# simpleCH552_finished.net
KiCad netlist of a schematic drawn in EAGLE
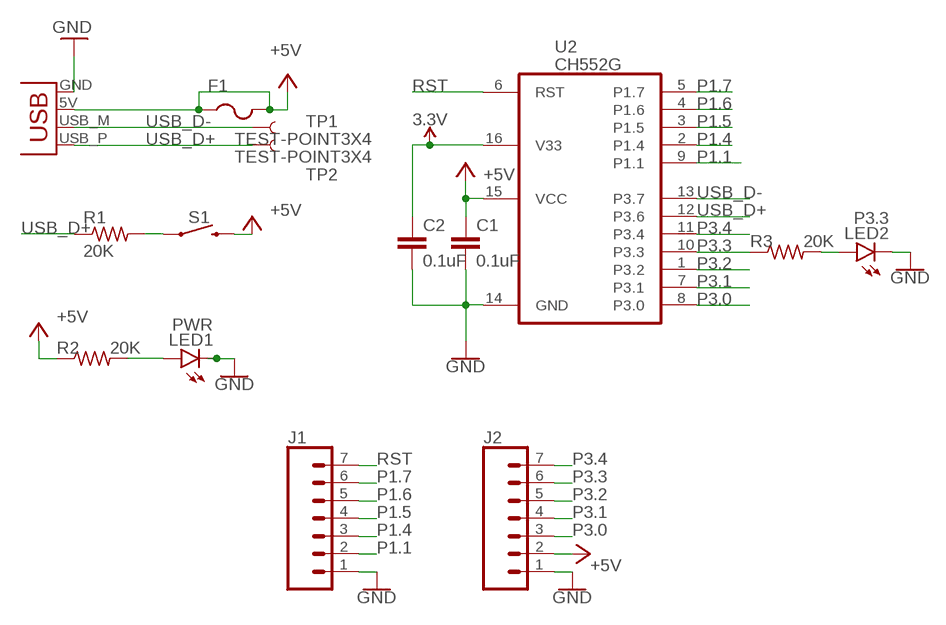
[diagram p0: schematic, sheet 1]

(export (version "E")
  (design (tool "Eeschema 10.0.6"))
  (components
    (comp (ref "C1")
      (value "0.1uF")
      (footprint "eagle-import:C0805K")
      (libsource (lib "eagle-import") (part "C-EUC0805K"))
    )
    (comp (ref "C2")
      (value "0.1uF")
      (footprint "eagle-import:C0805K")
      (libsource (lib "eagle-import") (part "C-EUC0805K"))
    )
    (comp (ref "F1")
      (value "PTCFUSE-1206")
      (footprint "eagle-import:R1206")
      (libsource (lib "eagle-import") (part "PTCFUSE-1206"))
    )
    (comp (ref "J1")
      (value "CONN_07NO_SILK")
      (footprint "eagle-import:1X07_NO_SILK")
      (libsource (lib "eagle-import") (part "CONN_07NO_SILK"))
    )
    (comp (ref "J2")
      (value "CONN_07NO_SILK")
      (footprint "eagle-import:1X07_NO_SILK")
      (libsource (lib "eagle-import") (part "CONN_07NO_SILK"))
    )
    (comp (ref "LED1")
      (value "PWR")
      (footprint "eagle-import:GHI-BASICCOMPONENTS_0805-LED")
      (libsource (lib "eagle-import") (part "GHI-BASICCOMPONENTS_LED-(INCH)-0805"))
    )
    (comp (ref "LED2")
      (value "P3.3")
      (footprint "eagle-import:GHI-BASICCOMPONENTS_0805-LED")
      (libsource (lib "eagle-import") (part "GHI-BASICCOMPONENTS_LED-(INCH)-0805"))
    )
    (comp (ref "R1")
      (value "20K")
      (footprint "eagle-import:R0805")
      (libsource (lib "eagle-import") (part "R-US_R0805"))
    )
    (comp (ref "R2")
      (value "20K")
      (footprint "eagle-import:R0805")
      (libsource (lib "eagle-import") (part "R-US_R0805"))
    )
    (comp (ref "R3")
      (value "20K")
      (footprint "eagle-import:R0805")
      (libsource (lib "eagle-import") (part "R-US_R0805"))
    )
    (comp (ref "S1")
      (value "MOMENTARY-SWITCH-SPST-SMD-6.2MM-TALL")
      (footprint "eagle-import:TACTILE_SWITCH_SMD_6.2MM_TALL")
      (libsource (lib "eagle-import") (part "MOMENTARY-SWITCH-SPST-SMD-6.2MM-TALL"))
    )
    (comp (ref "TP1")
      (value "TEST-POINT3X4")
      (footprint "eagle-import:PAD.03X.04")
      (libsource (lib "eagle-import") (part "TEST-POINT3X4"))
    )
    (comp (ref "TP2")
      (value "TEST-POINT3X4")
      (footprint "eagle-import:PAD.03X.04")
      (libsource (lib "eagle-import") (part "TEST-POINT3X4"))
    )
    (comp (ref "U2")
      (value "CH552G")
      (footprint "eagle-import:MY_IC_SO16")
      (libsource (lib "eagle-import") (part "MY_IC_CH551G_CH552GSOP-16"))
    )
    (comp (ref "X1")
      (value "USBPCB")
      (footprint "eagle-import:USB-A-PCB")
      (libsource (lib "eagle-import") (part "USBPCB"))
    )
  )
  (nets
    (net (code "1") (name "+5V") (class "Default")
      (node (ref "C1") (pin "1") (pinfunction "1_1") (pintype "passive"))
      (node (ref "F1") (pin "1") (pinfunction "1_1") (pintype "passive"))
      (node (ref "F1") (pin "2") (pinfunction "2_2") (pintype "passive"))
      (node (ref "J2") (pin "2") (pinfunction "2_2") (pintype "passive"))
      (node (ref "R2") (pin "1") (pinfunction "1_1") (pintype "passive"))
      (node (ref "S1") (pin "B2") (pinfunction "2_B2") (pintype "passive"))
      (node (ref "U2") (pin "15") (pinfunction "VCC_15") (pintype "power_in"))
      (node (ref "X1") (pin "5V") (pinfunction "VBUS_5V") (pintype "bidirectional"))
    )
    (net (code "2") (name "/P1.1") (class "Default")
      (node (ref "J1") (pin "2") (pinfunction "2_2") (pintype "passive"))
      (node (ref "U2") (pin "9") (pinfunction "P1.1_9") (pintype "bidirectional"))
    )
    (net (code "3") (name "/P1.4") (class "Default")
      (node (ref "J1") (pin "3") (pinfunction "3_3") (pintype "passive"))
      (node (ref "U2") (pin "2") (pinfunction "P1.4_2") (pintype "bidirectional"))
    )
    (net (code "4") (name "/P1.5") (class "Default")
      (node (ref "J1") (pin "4") (pinfunction "4_4") (pintype "passive"))
      (node (ref "U2") (pin "3") (pinfunction "P1.5_3") (pintype "bidirectional"))
    )
    (net (code "5") (name "/P1.6") (class "Default")
      (node (ref "J1") (pin "5") (pinfunction "5_5") (pintype "passive"))
      (node (ref "U2") (pin "4") (pinfunction "P1.6_4") (pintype "bidirectional"))
    )
    (net (code "6") (name "/P1.7") (class "Default")
      (node (ref "J1") (pin "6") (pinfunction "6_6") (pintype "passive"))
      (node (ref "U2") (pin "5") (pinfunction "P1.7_5") (pintype "bidirectional"))
    )
    (net (code "7") (name "/P3.0") (class "Default")
      (node (ref "J2") (pin "3") (pinfunction "3_3") (pintype "passive"))
      (node (ref "U2") (pin "8") (pinfunction "P3.0_8") (pintype "bidirectional"))
    )
    (net (code "8") (name "/P3.1") (class "Default")
      (node (ref "J2") (pin "4") (pinfunction "4_4") (pintype "passive"))
      (node (ref "U2") (pin "7") (pinfunction "P3.1_7") (pintype "bidirectional"))
    )
    (net (code "9") (name "/P3.2") (class "Default")
      (node (ref "J2") (pin "5") (pinfunction "5_5") (pintype "passive"))
      (node (ref "U2") (pin "1") (pinfunction "P3.2_1") (pintype "bidirectional"))
    )
    (net (code "10") (name "/P3.3") (class "Default")
      (node (ref "J2") (pin "6") (pinfunction "6_6") (pintype "passive"))
      (node (ref "R3") (pin "1") (pinfunction "1_1") (pintype "passive"))
      (node (ref "U2") (pin "10") (pinfunction "P3.3_10") (pintype "bidirectional"))
    )
    (net (code "11") (name "/P3.4") (class "Default")
      (node (ref "J2") (pin "7") (pinfunction "7_7") (pintype "passive"))
      (node (ref "U2") (pin "11") (pinfunction "P3.4_11") (pintype "bidirectional"))
    )
    (net (code "12") (name "/RST") (class "Default")
      (node (ref "J1") (pin "7") (pinfunction "7_7") (pintype "passive"))
      (node (ref "U2") (pin "6") (pinfunction "RST_6") (pintype "input"))
    )
    (net (code "13") (name "/USB_D+") (class "Default")
      (node (ref "R1") (pin "1") (pinfunction "1_1") (pintype "passive"))
      (node (ref "TP2") (pin "P$1") (pinfunction "1_P$1") (pintype "bidirectional"))
      (node (ref "U2") (pin "12") (pinfunction "P3.6_12") (pintype "bidirectional"))
      (node (ref "X1") (pin "USB_P") (pinfunction "D+_USB_P") (pintype "bidirectional"))
    )
    (net (code "14") (name "/USB_D-") (class "Default")
      (node (ref "TP1") (pin "P$1") (pinfunction "1_P$1") (pintype "bidirectional"))
      (node (ref "U2") (pin "13") (pinfunction "P3.7_13") (pintype "bidirectional"))
      (node (ref "X1") (pin "USB_M") (pinfunction "D-_USB_M") (pintype "bidirectional"))
    )
    (net (code "15") (name "3.3V") (class "Default")
      (node (ref "C2") (pin "1") (pinfunction "1_1") (pintype "passive"))
      (node (ref "U2") (pin "16") (pinfunction "V33_16") (pintype "power_in"))
    )
    (net (code "16") (name "GND") (class "Default")
      (node (ref "C1") (pin "2") (pinfunction "2_2") (pintype "passive"))
      (node (ref "C2") (pin "2") (pinfunction "2_2") (pintype "passive"))
      (node (ref "J1") (pin "1") (pinfunction "1_1") (pintype "passive"))
      (node (ref "J2") (pin "1") (pinfunction "1_1") (pintype "passive"))
      (node (ref "LED1") (pin "K") (pinfunction "K_K") (pintype "passive"))
      (node (ref "LED2") (pin "K") (pinfunction "K_K") (pintype "passive"))
      (node (ref "U2") (pin "14") (pinfunction "GND_14") (pintype "power_in"))
      (node (ref "X1") (pin "GND") (pinfunction "GND_GND") (pintype "bidirectional"))
    )
    (net (code "17") (name "Net-(LED1-PadA)") (class "Default")
      (node (ref "LED1") (pin "A") (pinfunction "A_A") (pintype "passive"))
      (node (ref "R2") (pin "2") (pinfunction "2_2") (pintype "passive"))
    )
    (net (code "18") (name "Net-(LED2-PadA)") (class "Default")
      (node (ref "LED2") (pin "A") (pinfunction "A_A") (pintype "passive"))
      (node (ref "R3") (pin "2") (pinfunction "2_2") (pintype "passive"))
    )
    (net (code "19") (name "Net-(S1-1)") (class "Default")
      (node (ref "R1") (pin "2") (pinfunction "2_2") (pintype "passive"))
      (node (ref "S1") (pin "A2") (pinfunction "1_A2") (pintype "passive"))
    )
  )
)
